# DefuseIt01.net
KiCad netlist of a schematic drawn in EAGLE
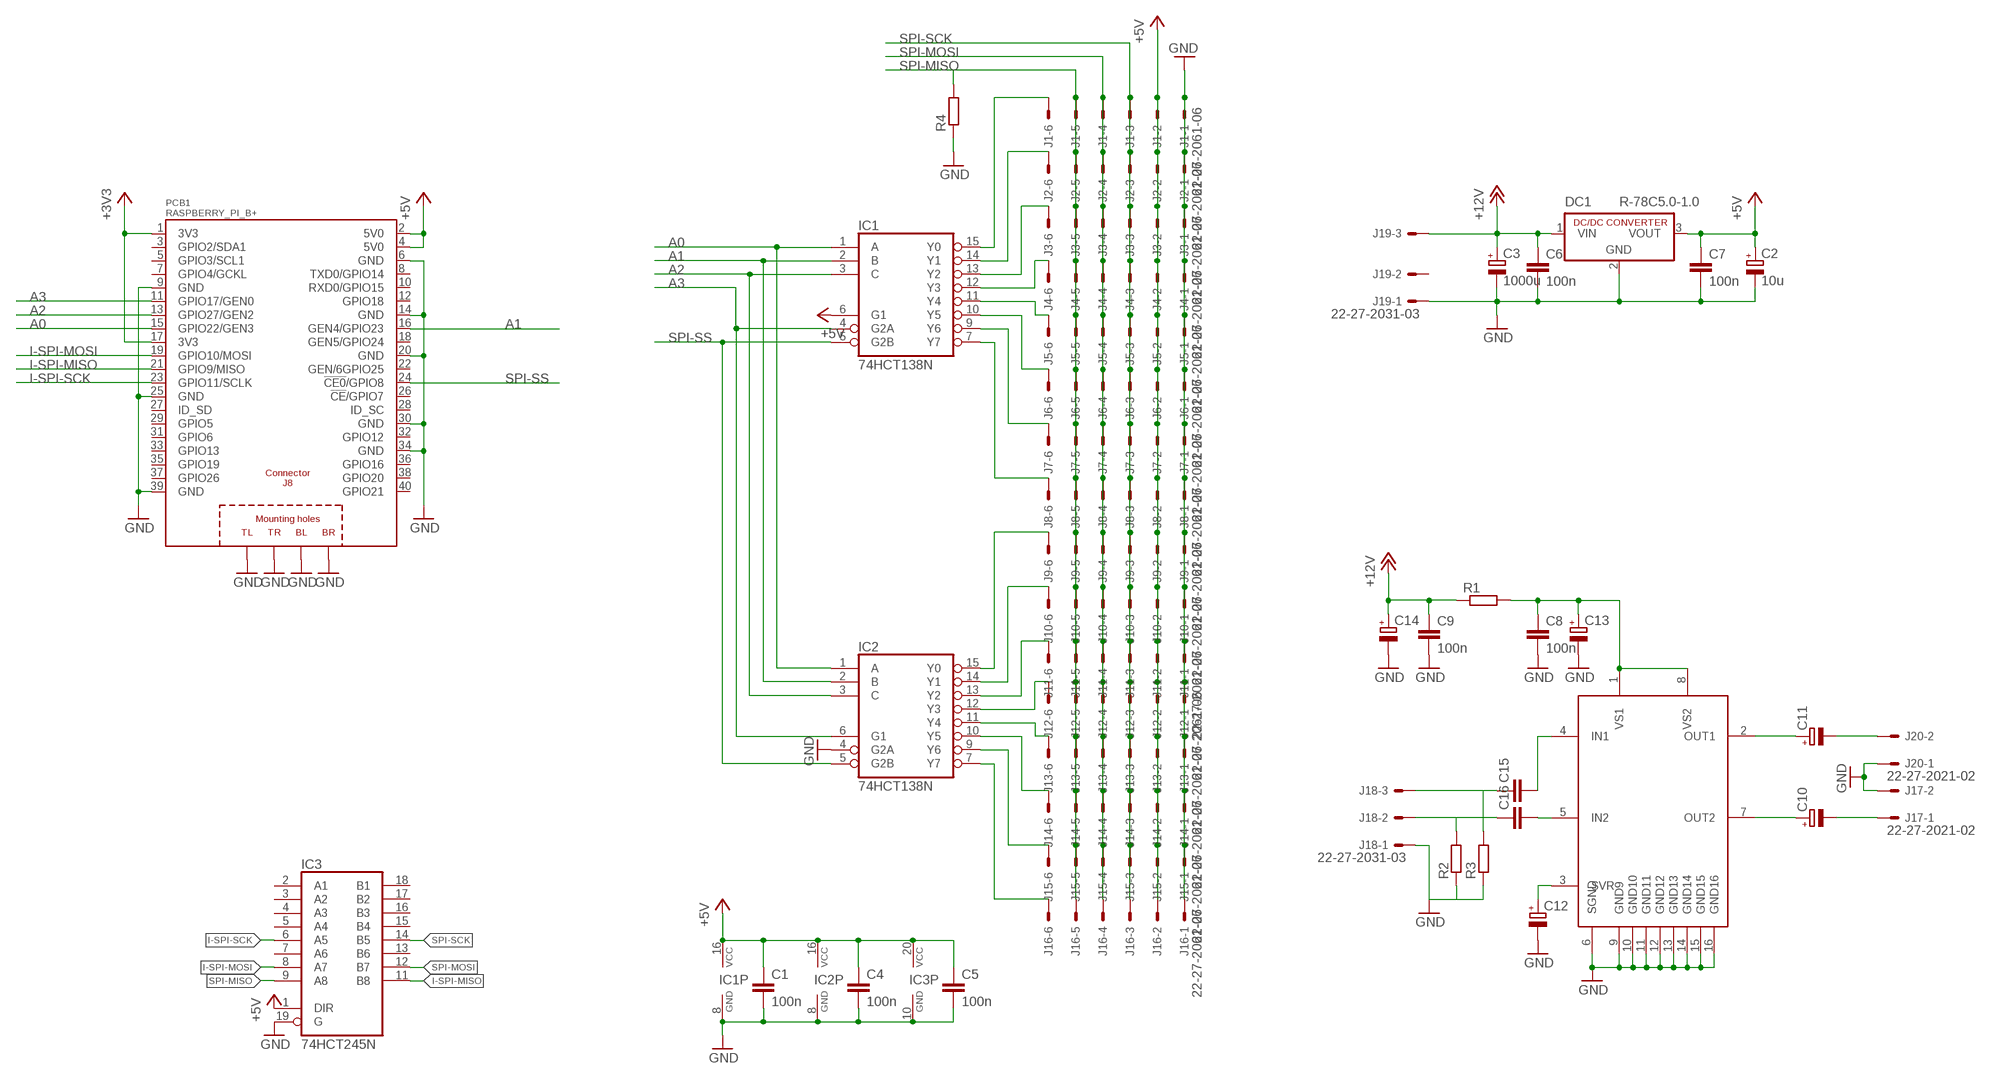
[diagram p0: schematic, sheet 1]

(export (version "E")
  (design (tool "Eeschema 10.0.6"))
  (components
    (comp (ref "C1")
      (value "100n")
      (footprint "eagle-import:C025-025X050")
      (libsource (lib "eagle-import") (part "C-EU025-025X050"))
    )
    (comp (ref "C2")
      (value "10u")
      (footprint "eagle-import:E3,5-8")
      (libsource (lib "eagle-import") (part "CPOL-EUE3.5-8"))
    )
    (comp (ref "C3")
      (value "1000u")
      (footprint "eagle-import:E7,5-16")
      (libsource (lib "eagle-import") (part "CPOL-EUE7.5-16"))
    )
    (comp (ref "C4")
      (value "100n")
      (footprint "eagle-import:C025-025X050")
      (libsource (lib "eagle-import") (part "C-EU025-025X050"))
    )
    (comp (ref "C5")
      (value "100n")
      (footprint "eagle-import:C025-025X050")
      (libsource (lib "eagle-import") (part "C-EU025-025X050"))
    )
    (comp (ref "C6")
      (value "100n")
      (footprint "eagle-import:C025-025X050")
      (libsource (lib "eagle-import") (part "C-EU025-025X050"))
    )
    (comp (ref "C7")
      (value "100n")
      (footprint "eagle-import:C025-025X050")
      (libsource (lib "eagle-import") (part "C-EU025-025X050"))
    )
    (comp (ref "C8")
      (value "100n")
      (footprint "eagle-import:C025-025X050")
      (libsource (lib "eagle-import") (part "C-EU025-025X050"))
    )
    (comp (ref "C9")
      (value "100n")
      (footprint "eagle-import:C025-025X050")
      (libsource (lib "eagle-import") (part "C-EU025-025X050"))
    )
    (comp (ref "C10")
      (value "CPOL-EUE3.5-8")
      (footprint "eagle-import:E3,5-8")
      (libsource (lib "eagle-import") (part "CPOL-EUE3.5-8"))
    )
    (comp (ref "C11")
      (value "CPOL-EUE3.5-8")
      (footprint "eagle-import:E3,5-8")
      (libsource (lib "eagle-import") (part "CPOL-EUE3.5-8"))
    )
    (comp (ref "C12")
      (value "CPOL-EUE2.5-5")
      (footprint "eagle-import:E2,5-5")
      (libsource (lib "eagle-import") (part "CPOL-EUE2.5-5"))
    )
    (comp (ref "C13")
      (value "CPOL-EUE2.5-5")
      (footprint "eagle-import:E2,5-5")
      (libsource (lib "eagle-import") (part "CPOL-EUE2.5-5"))
    )
    (comp (ref "C14")
      (value "CPOL-EUE2.5-5")
      (footprint "eagle-import:E2,5-5")
      (libsource (lib "eagle-import") (part "CPOL-EUE2.5-5"))
    )
    (comp (ref "C15")
      (value "C-EU050-030X075")
      (footprint "eagle-import:C050-030X075")
      (libsource (lib "eagle-import") (part "C-EU050-030X075"))
    )
    (comp (ref "C16")
      (value "C-EU050-030X075")
      (footprint "eagle-import:C050-030X075")
      (libsource (lib "eagle-import") (part "C-EU050-030X075"))
    )
    (comp (ref "DC1")
      (value "R-78C5.0-1.0")
      (footprint "eagle-import:SIP3")
      (libsource (lib "eagle-import") (part "R-78C-1.05.0"))
    )
    (comp (ref "IC1")
      (value "74HCT138N")
      (footprint "eagle-import:DIL16")
      (libsource (lib "eagle-import") (part "74138NHCT"))
    )
    (comp (ref "IC2")
      (value "74HCT138N")
      (footprint "eagle-import:DIL16")
      (libsource (lib "eagle-import") (part "74138NHCT"))
    )
    (comp (ref "IC3")
      (value "74HCT245N")
      (footprint "eagle-import:DIL20")
      (libsource (lib "eagle-import") (part "74245NHCT"))
    )
    (comp (ref "J1")
      (value "22-27-2061-06")
      (footprint "eagle-import:6410-06")
      (libsource (lib "eagle-import") (part "22-?-0627-2061"))
    )
    (comp (ref "J2")
      (value "22-27-2061-06")
      (footprint "eagle-import:6410-06")
      (libsource (lib "eagle-import") (part "22-?-0627-2061"))
    )
    (comp (ref "J3")
      (value "22-27-2061-06")
      (footprint "eagle-import:6410-06")
      (libsource (lib "eagle-import") (part "22-?-0627-2061"))
    )
    (comp (ref "J4")
      (value "22-27-2061-06")
      (footprint "eagle-import:6410-06")
      (libsource (lib "eagle-import") (part "22-?-0627-2061"))
    )
    (comp (ref "J5")
      (value "22-27-2061-06")
      (footprint "eagle-import:6410-06")
      (libsource (lib "eagle-import") (part "22-?-0627-2061"))
    )
    (comp (ref "J6")
      (value "22-27-2061-06")
      (footprint "eagle-import:6410-06")
      (libsource (lib "eagle-import") (part "22-?-0627-2061"))
    )
    (comp (ref "J7")
      (value "22-27-2061-06")
      (footprint "eagle-import:6410-06")
      (libsource (lib "eagle-import") (part "22-?-0627-2061"))
    )
    (comp (ref "J8")
      (value "22-27-2061-06")
      (footprint "eagle-import:6410-06")
      (libsource (lib "eagle-import") (part "22-?-0627-2061"))
    )
    (comp (ref "J9")
      (value "22-27-2061-06")
      (footprint "eagle-import:6410-06")
      (libsource (lib "eagle-import") (part "22-?-0627-2061"))
    )
    (comp (ref "J10")
      (value "22-27-2061-06")
      (footprint "eagle-import:6410-06")
      (libsource (lib "eagle-import") (part "22-?-0627-2061"))
    )
    (comp (ref "J11")
      (value "22-27-2061-06")
      (footprint "eagle-import:6410-06")
      (libsource (lib "eagle-import") (part "22-?-0627-2061"))
    )
    (comp (ref "J12")
      (value "22-27-2061-06")
      (footprint "eagle-import:6410-06")
      (libsource (lib "eagle-import") (part "22-?-0627-2061"))
    )
    (comp (ref "J13")
      (value "22-27-2061-06")
      (footprint "eagle-import:6410-06")
      (libsource (lib "eagle-import") (part "22-?-0627-2061"))
    )
    (comp (ref "J14")
      (value "22-27-2061-06")
      (footprint "eagle-import:6410-06")
      (libsource (lib "eagle-import") (part "22-?-0627-2061"))
    )
    (comp (ref "J15")
      (value "22-27-2061-06")
      (footprint "eagle-import:6410-06")
      (libsource (lib "eagle-import") (part "22-?-0627-2061"))
    )
    (comp (ref "J16")
      (value "22-27-2061-06")
      (footprint "eagle-import:6410-06")
      (libsource (lib "eagle-import") (part "22-?-0627-2061"))
    )
    (comp (ref "J17")
      (value "22-27-2021-02")
      (footprint "eagle-import:6410-02")
      (libsource (lib "eagle-import") (part "22-?-0227-2021"))
    )
    (comp (ref "J18")
      (value "22-27-2031-03")
      (footprint "eagle-import:6410-03")
      (libsource (lib "eagle-import") (part "22-?-0327-2031"))
    )
    (comp (ref "J19")
      (value "22-27-2031-03")
      (footprint "eagle-import:6410-03")
      (libsource (lib "eagle-import") (part "22-?-0327-2031"))
    )
    (comp (ref "J20")
      (value "22-27-2021-02")
      (footprint "eagle-import:6410-02")
      (libsource (lib "eagle-import") (part "22-?-0227-2021"))
    )
    (comp (ref "PCB1")
      (value "RASPBERRY_PI_B+")
      (footprint "eagle-import:RASPBERRY_PI_B+")
      (libsource (lib "eagle-import") (part "RASPBERRY_PI_B+"))
    )
    (comp (ref "R1")
      (value "R-EU_0207/10")
      (footprint "eagle-import:0207_10")
      (libsource (lib "eagle-import") (part "R-EU_0207/10"))
    )
    (comp (ref "R2")
      (value "R-EU_0207/10")
      (footprint "eagle-import:0207_10")
      (libsource (lib "eagle-import") (part "R-EU_0207/10"))
    )
    (comp (ref "R3")
      (value "R-EU_0207/10")
      (footprint "eagle-import:0207_10")
      (libsource (lib "eagle-import") (part "R-EU_0207/10"))
    )
    (comp (ref "R4")
      (value "R-EU_0207/10")
      (footprint "eagle-import:0207_10")
      (libsource (lib "eagle-import") (part "R-EU_0207/10"))
    )
    (comp (ref "U$1")
      (value "TDA7268")
      (footprint "eagle-import:DIL16")
      (libsource (lib "eagle-import") (part "TDA7268"))
    )
  )
  (nets
    (net (code "1") (name "+3V3") (class "Default")
      (node (ref "PCB1") (pin "1") (pinfunction "3V3_1") (pintype "power_in"))
      (node (ref "PCB1") (pin "17") (pinfunction "3V3_17") (pintype "power_in"))
    )
    (net (code "2") (name "+5V") (class "Default")
      (node (ref "C1") (pin "1") (pinfunction "1_1") (pintype "passive"))
      (node (ref "C2") (pin "+") (pinfunction "+_+") (pintype "passive"))
      (node (ref "C4") (pin "1") (pinfunction "1_1") (pintype "passive"))
      (node (ref "C5") (pin "1") (pinfunction "1_1") (pintype "passive"))
      (node (ref "C7") (pin "1") (pinfunction "1_1") (pintype "passive"))
      (node (ref "DC1") (pin "3") (pinfunction "VOUT_3") (pintype "passive"))
      (node (ref "IC1") (pin "16") (pinfunction "VCC_16") (pintype "power_in"))
      (node (ref "IC1") (pin "6") (pinfunction "G1_6") (pintype "input"))
      (node (ref "IC2") (pin "16") (pinfunction "VCC_16") (pintype "power_in"))
      (node (ref "IC3") (pin "1") (pinfunction "DIR_1") (pintype "input"))
      (node (ref "IC3") (pin "20") (pinfunction "VCC_20") (pintype "power_in"))
      (node (ref "J1") (pin "2") (pinfunction "S_2") (pintype "passive"))
      (node (ref "J10") (pin "2") (pinfunction "S_2") (pintype "passive"))
      (node (ref "J11") (pin "2") (pinfunction "S_2") (pintype "passive"))
      (node (ref "J12") (pin "2") (pinfunction "S_2") (pintype "passive"))
      (node (ref "J13") (pin "2") (pinfunction "S_2") (pintype "passive"))
      (node (ref "J14") (pin "2") (pinfunction "S_2") (pintype "passive"))
      (node (ref "J15") (pin "2") (pinfunction "S_2") (pintype "passive"))
      (node (ref "J16") (pin "2") (pinfunction "S_2") (pintype "passive"))
      (node (ref "J2") (pin "2") (pinfunction "S_2") (pintype "passive"))
      (node (ref "J3") (pin "2") (pinfunction "S_2") (pintype "passive"))
      (node (ref "J4") (pin "2") (pinfunction "S_2") (pintype "passive"))
      (node (ref "J5") (pin "2") (pinfunction "S_2") (pintype "passive"))
      (node (ref "J6") (pin "2") (pinfunction "S_2") (pintype "passive"))
      (node (ref "J7") (pin "2") (pinfunction "S_2") (pintype "passive"))
      (node (ref "J8") (pin "2") (pinfunction "S_2") (pintype "passive"))
      (node (ref "J9") (pin "2") (pinfunction "S_2") (pintype "passive"))
      (node (ref "PCB1") (pin "2") (pinfunction "5V0_2") (pintype "power_in"))
      (node (ref "PCB1") (pin "4") (pinfunction "5V0_4") (pintype "power_in"))
    )
    (net (code "3") (name "+12V") (class "Default")
      (node (ref "C14") (pin "+") (pinfunction "+_+") (pintype "passive"))
      (node (ref "C3") (pin "+") (pinfunction "+_+") (pintype "passive"))
      (node (ref "C6") (pin "1") (pinfunction "1_1") (pintype "passive"))
      (node (ref "C9") (pin "1") (pinfunction "1_1") (pintype "passive"))
      (node (ref "DC1") (pin "1") (pinfunction "VIN_1") (pintype "passive"))
      (node (ref "J19") (pin "3") (pinfunction "S_3") (pintype "passive"))
      (node (ref "R1") (pin "1") (pinfunction "1_1") (pintype "passive"))
    )
    (net (code "4") (name "/A0") (class "Default")
      (node (ref "IC1") (pin "1") (pinfunction "A_1") (pintype "input"))
      (node (ref "IC2") (pin "1") (pinfunction "A_1") (pintype "input"))
      (node (ref "PCB1") (pin "15") (pinfunction "GPIO22/GEN3_15") (pintype "bidirectional"))
    )
    (net (code "5") (name "/A1") (class "Default")
      (node (ref "IC1") (pin "2") (pinfunction "B_2") (pintype "input"))
      (node (ref "IC2") (pin "2") (pinfunction "B_2") (pintype "input"))
      (node (ref "PCB1") (pin "16") (pinfunction "GEN4/GPIO23_16") (pintype "bidirectional"))
    )
    (net (code "6") (name "/A2") (class "Default")
      (node (ref "IC1") (pin "3") (pinfunction "C_3") (pintype "input"))
      (node (ref "IC2") (pin "3") (pinfunction "C_3") (pintype "input"))
      (node (ref "PCB1") (pin "13") (pinfunction "GPIO27/GEN2_13") (pintype "bidirectional"))
    )
    (net (code "7") (name "/A3") (class "Default")
      (node (ref "IC1") (pin "4") (pinfunction "G2A_4") (pintype "input"))
      (node (ref "IC2") (pin "6") (pinfunction "G1_6") (pintype "input"))
      (node (ref "PCB1") (pin "11") (pinfunction "GPIO17/GEN0_11") (pintype "bidirectional"))
    )
    (net (code "8") (name "/SPI-SS") (class "Default")
      (node (ref "IC1") (pin "5") (pinfunction "G2B_5") (pintype "input"))
      (node (ref "IC2") (pin "5") (pinfunction "G2B_5") (pintype "input"))
      (node (ref "PCB1") (pin "24") (pinfunction "~{CE0}/GPIO8_24") (pintype "bidirectional"))
    )
    (net (code "9") (name "GND") (class "Default")
      (node (ref "C1") (pin "2") (pinfunction "2_2") (pintype "passive"))
      (node (ref "C12") (pin "-") (pinfunction "-_-") (pintype "passive"))
      (node (ref "C13") (pin "-") (pinfunction "-_-") (pintype "passive"))
      (node (ref "C14") (pin "-") (pinfunction "-_-") (pintype "passive"))
      (node (ref "C2") (pin "-") (pinfunction "-_-") (pintype "passive"))
      (node (ref "C3") (pin "-") (pinfunction "-_-") (pintype "passive"))
      (node (ref "C4") (pin "2") (pinfunction "2_2") (pintype "passive"))
      (node (ref "C5") (pin "2") (pinfunction "2_2") (pintype "passive"))
      (node (ref "C6") (pin "2") (pinfunction "2_2") (pintype "passive"))
      (node (ref "C7") (pin "2") (pinfunction "2_2") (pintype "passive"))
      (node (ref "C8") (pin "2") (pinfunction "2_2") (pintype "passive"))
      (node (ref "C9") (pin "2") (pinfunction "2_2") (pintype "passive"))
      (node (ref "DC1") (pin "2") (pinfunction "GND_2") (pintype "passive"))
      (node (ref "IC1") (pin "8") (pinfunction "GND_8") (pintype "power_in"))
      (node (ref "IC2") (pin "4") (pinfunction "G2A_4") (pintype "input"))
      (node (ref "IC2") (pin "8") (pinfunction "GND_8") (pintype "power_in"))
      (node (ref "IC3") (pin "10") (pinfunction "GND_10") (pintype "power_in"))
      (node (ref "IC3") (pin "19") (pinfunction "G_19") (pintype "input"))
      (node (ref "J1") (pin "1") (pinfunction "S_1") (pintype "passive"))
      (node (ref "J10") (pin "1") (pinfunction "S_1") (pintype "passive"))
      (node (ref "J11") (pin "1") (pinfunction "S_1") (pintype "passive"))
      (node (ref "J12") (pin "1") (pinfunction "S_1") (pintype "passive"))
      (node (ref "J13") (pin "1") (pinfunction "S_1") (pintype "passive"))
      (node (ref "J14") (pin "1") (pinfunction "S_1") (pintype "passive"))
      (node (ref "J15") (pin "1") (pinfunction "S_1") (pintype "passive"))
      (node (ref "J16") (pin "1") (pinfunction "S_1") (pintype "passive"))
      (node (ref "J17") (pin "2") (pinfunction "S_2") (pintype "passive"))
      (node (ref "J18") (pin "1") (pinfunction "S_1") (pintype "passive"))
      (node (ref "J19") (pin "1") (pinfunction "S_1") (pintype "passive"))
      (node (ref "J2") (pin "1") (pinfunction "S_1") (pintype "passive"))
      (node (ref "J20") (pin "1") (pinfunction "S_1") (pintype "passive"))
      (node (ref "J3") (pin "1") (pinfunction "S_1") (pintype "passive"))
      (node (ref "J4") (pin "1") (pinfunction "S_1") (pintype "passive"))
      (node (ref "J5") (pin "1") (pinfunction "S_1") (pintype "passive"))
      (node (ref "J6") (pin "1") (pinfunction "S_1") (pintype "passive"))
      (node (ref "J7") (pin "1") (pinfunction "S_1") (pintype "passive"))
      (node (ref "J8") (pin "1") (pinfunction "S_1") (pintype "passive"))
      (node (ref "J9") (pin "1") (pinfunction "S_1") (pintype "passive"))
      (node (ref "PCB1") (pin "14") (pinfunction "GND_14") (pintype "power_in"))
      (node (ref "PCB1") (pin "20") (pinfunction "GND_20") (pintype "power_in"))
      (node (ref "PCB1") (pin "25") (pinfunction "GND_25") (pintype "power_in"))
      (node (ref "PCB1") (pin "30") (pinfunction "GND_30") (pintype "power_in"))
      (node (ref "PCB1") (pin "34") (pinfunction "GND_34") (pintype "power_in"))
      (node (ref "PCB1") (pin "39") (pinfunction "GND_39") (pintype "power_in"))
      (node (ref "PCB1") (pin "6") (pinfunction "GND_6") (pintype "power_in"))
      (node (ref "PCB1") (pin "9") (pinfunction "GND_9") (pintype "power_in"))
      (node (ref "PCB1") (pin "PE_BL") (pinfunction "BL_PE_BL") (pintype "bidirectional"))
      (node (ref "PCB1") (pin "PE_BR") (pinfunction "BR_PE_BR") (pintype "bidirectional"))
      (node (ref "PCB1") (pin "PE_TL") (pinfunction "TL_PE_TL") (pintype "bidirectional"))
      (node (ref "PCB1") (pin "PE_TR") (pinfunction "TR_PE_TR") (pintype "bidirectional"))
      (node (ref "R2") (pin "1") (pinfunction "1_1") (pintype "passive"))
      (node (ref "R3") (pin "1") (pinfunction "1_1") (pintype "passive"))
      (node (ref "R4") (pin "1") (pinfunction "1_1") (pintype "passive"))
      (node (ref "U$1") (pin "10") (pinfunction "GND10_10") (pintype "bidirectional"))
      (node (ref "U$1") (pin "11") (pinfunction "GND11_11") (pintype "bidirectional"))
      (node (ref "U$1") (pin "12") (pinfunction "GND12_12") (pintype "bidirectional"))
      (node (ref "U$1") (pin "13") (pinfunction "GND13_13") (pintype "bidirectional"))
      (node (ref "U$1") (pin "14") (pinfunction "GND14_14") (pintype "bidirectional"))
      (node (ref "U$1") (pin "15") (pinfunction "GND15_15") (pintype "bidirectional"))
      (node (ref "U$1") (pin "16") (pinfunction "GND16_16") (pintype "bidirectional"))
      (node (ref "U$1") (pin "6") (pinfunction "SGND_6") (pintype "bidirectional"))
      (node (ref "U$1") (pin "9") (pinfunction "GND9_9") (pintype "bidirectional"))
    )
    (net (code "10") (name "I-SPI-MISO") (class "Default")
      (node (ref "IC3") (pin "11") (pinfunction "B8_11") (pintype "bidirectional"))
      (node (ref "PCB1") (pin "21") (pinfunction "GPIO9/MISO_21") (pintype "bidirectional"))
    )
    (net (code "11") (name "I-SPI-MOSI") (class "Default")
      (node (ref "IC3") (pin "8") (pinfunction "A7_8") (pintype "bidirectional"))
      (node (ref "PCB1") (pin "19") (pinfunction "GPIO10/MOSI_19") (pintype "bidirectional"))
    )
    (net (code "12") (name "I-SPI-SCK") (class "Default")
      (node (ref "IC3") (pin "6") (pinfunction "A5_6") (pintype "bidirectional"))
      (node (ref "PCB1") (pin "23") (pinfunction "GPIO11/SCLK_23") (pintype "bidirectional"))
    )
    (net (code "13") (name "Net-(IC1A-Y0)") (class "Default")
      (node (ref "IC1") (pin "15") (pinfunction "Y0_15") (pintype "output"))
      (node (ref "J1") (pin "6") (pinfunction "S_6") (pintype "passive"))
    )
    (net (code "14") (name "Net-(IC1A-Y1)") (class "Default")
      (node (ref "IC1") (pin "14") (pinfunction "Y1_14") (pintype "output"))
      (node (ref "J2") (pin "6") (pinfunction "S_6") (pintype "passive"))
    )
    (net (code "15") (name "Net-(IC1A-Y2)") (class "Default")
      (node (ref "IC1") (pin "13") (pinfunction "Y2_13") (pintype "output"))
      (node (ref "J3") (pin "6") (pinfunction "S_6") (pintype "passive"))
    )
    (net (code "16") (name "Net-(IC1A-Y3)") (class "Default")
      (node (ref "IC1") (pin "12") (pinfunction "Y3_12") (pintype "output"))
      (node (ref "J4") (pin "6") (pinfunction "S_6") (pintype "passive"))
    )
    (net (code "17") (name "Net-(IC1A-Y4)") (class "Default")
      (node (ref "IC1") (pin "11") (pinfunction "Y4_11") (pintype "output"))
      (node (ref "J5") (pin "6") (pinfunction "S_6") (pintype "passive"))
    )
    (net (code "18") (name "Net-(IC1A-Y5)") (class "Default")
      (node (ref "IC1") (pin "10") (pinfunction "Y5_10") (pintype "output"))
      (node (ref "J6") (pin "6") (pinfunction "S_6") (pintype "passive"))
    )
    (net (code "19") (name "Net-(IC1A-Y6)") (class "Default")
      (node (ref "IC1") (pin "9") (pinfunction "Y6_9") (pintype "output"))
      (node (ref "J7") (pin "6") (pinfunction "S_6") (pintype "passive"))
    )
    (net (code "20") (name "Net-(IC1A-Y7)") (class "Default")
      (node (ref "IC1") (pin "7") (pinfunction "Y7_7") (pintype "output"))
      (node (ref "J8") (pin "6") (pinfunction "S_6") (pintype "passive"))
    )
    (net (code "21") (name "Net-(IC2A-Y0)") (class "Default")
      (node (ref "IC2") (pin "15") (pinfunction "Y0_15") (pintype "output"))
      (node (ref "J9") (pin "6") (pinfunction "S_6") (pintype "passive"))
    )
    (net (code "22") (name "Net-(IC2A-Y1)") (class "Default")
      (node (ref "IC2") (pin "14") (pinfunction "Y1_14") (pintype "output"))
      (node (ref "J10") (pin "6") (pinfunction "S_6") (pintype "passive"))
    )
    (net (code "23") (name "Net-(IC2A-Y2)") (class "Default")
      (node (ref "IC2") (pin "13") (pinfunction "Y2_13") (pintype "output"))
      (node (ref "J11") (pin "6") (pinfunction "S_6") (pintype "passive"))
    )
    (net (code "24") (name "Net-(IC2A-Y3)") (class "Default")
      (node (ref "IC2") (pin "12") (pinfunction "Y3_12") (pintype "output"))
      (node (ref "J12") (pin "6") (pinfunction "S_6") (pintype "passive"))
    )
    (net (code "25") (name "Net-(IC2A-Y4)") (class "Default")
      (node (ref "IC2") (pin "11") (pinfunction "Y4_11") (pintype "output"))
      (node (ref "J13") (pin "6") (pinfunction "S_6") (pintype "passive"))
    )
    (net (code "26") (name "Net-(IC2A-Y5)") (class "Default")
      (node (ref "IC2") (pin "10") (pinfunction "Y5_10") (pintype "output"))
      (node (ref "J14") (pin "6") (pinfunction "S_6") (pintype "passive"))
    )
    (net (code "27") (name "Net-(IC2A-Y6)") (class "Default")
      (node (ref "IC2") (pin "9") (pinfunction "Y6_9") (pintype "output"))
      (node (ref "J15") (pin "6") (pinfunction "S_6") (pintype "passive"))
    )
    (net (code "28") (name "Net-(IC2A-Y7)") (class "Default")
      (node (ref "IC2") (pin "7") (pinfunction "Y7_7") (pintype "output"))
      (node (ref "J16") (pin "6") (pinfunction "S_6") (pintype "passive"))
    )
    (net (code "29") (name "Net-(J17A-S)") (class "Default")
      (node (ref "C10") (pin "-") (pinfunction "-_-") (pintype "passive"))
      (node (ref "J17") (pin "1") (pinfunction "S_1") (pintype "passive"))
    )
    (net (code "30") (name "Net-(J18B-S)") (class "Default")
      (node (ref "C16") (pin "1") (pinfunction "1_1") (pintype "passive"))
      (node (ref "J18") (pin "2") (pinfunction "S_2") (pintype "passive"))
      (node (ref "R2") (pin "2") (pinfunction "2_2") (pintype "passive"))
    )
    (net (code "31") (name "Net-(J18C-S)") (class "Default")
      (node (ref "C15") (pin "1") (pinfunction "1_1") (pintype "passive"))
      (node (ref "J18") (pin "3") (pinfunction "S_3") (pintype "passive"))
      (node (ref "R3") (pin "2") (pinfunction "2_2") (pintype "passive"))
    )
    (net (code "32") (name "Net-(J20B-S)") (class "Default")
      (node (ref "C11") (pin "-") (pinfunction "-_-") (pintype "passive"))
      (node (ref "J20") (pin "2") (pinfunction "S_2") (pintype "passive"))
    )
    (net (code "33") (name "Net-(U$1-IN1)") (class "Default")
      (node (ref "C15") (pin "2") (pinfunction "2_2") (pintype "passive"))
      (node (ref "U$1") (pin "4") (pinfunction "IN1_4") (pintype "bidirectional"))
    )
    (net (code "34") (name "Net-(U$1-IN2)") (class "Default")
      (node (ref "C16") (pin "2") (pinfunction "2_2") (pintype "passive"))
      (node (ref "U$1") (pin "5") (pinfunction "IN2_5") (pintype "bidirectional"))
    )
    (net (code "35") (name "Net-(U$1-OUT1)") (class "Default")
      (node (ref "C11") (pin "+") (pinfunction "+_+") (pintype "passive"))
      (node (ref "U$1") (pin "2") (pinfunction "OUT1_2") (pintype "bidirectional"))
    )
    (net (code "36") (name "Net-(U$1-OUT2)") (class "Default")
      (node (ref "C10") (pin "+") (pinfunction "+_+") (pintype "passive"))
      (node (ref "U$1") (pin "7") (pinfunction "OUT2_7") (pintype "bidirectional"))
    )
    (net (code "37") (name "Net-(U$1-SVR)") (class "Default")
      (node (ref "C12") (pin "+") (pinfunction "+_+") (pintype "passive"))
      (node (ref "U$1") (pin "3") (pinfunction "SVR_3") (pintype "bidirectional"))
    )
    (net (code "38") (name "Net-(U$1-VS1)") (class "Default")
      (node (ref "C13") (pin "+") (pinfunction "+_+") (pintype "passive"))
      (node (ref "C8") (pin "1") (pinfunction "1_1") (pintype "passive"))
      (node (ref "R1") (pin "2") (pinfunction "2_2") (pintype "passive"))
      (node (ref "U$1") (pin "1") (pinfunction "VS1_1") (pintype "bidirectional"))
      (node (ref "U$1") (pin "8") (pinfunction "VS2_8") (pintype "bidirectional"))
    )
    (net (code "39") (name "SPI-MISO") (class "Default")
      (node (ref "IC3") (pin "9") (pinfunction "A8_9") (pintype "bidirectional"))
      (node (ref "J1") (pin "5") (pinfunction "S_5") (pintype "passive"))
      (node (ref "J10") (pin "5") (pinfunction "S_5") (pintype "passive"))
      (node (ref "J11") (pin "5") (pinfunction "S_5") (pintype "passive"))
      (node (ref "J12") (pin "5") (pinfunction "S_5") (pintype "passive"))
      (node (ref "J13") (pin "5") (pinfunction "S_5") (pintype "passive"))
      (node (ref "J14") (pin "5") (pinfunction "S_5") (pintype "passive"))
      (node (ref "J15") (pin "5") (pinfunction "S_5") (pintype "passive"))
      (node (ref "J16") (pin "5") (pinfunction "S_5") (pintype "passive"))
      (node (ref "J2") (pin "5") (pinfunction "S_5") (pintype "passive"))
      (node (ref "J3") (pin "5") (pinfunction "S_5") (pintype "passive"))
      (node (ref "J4") (pin "5") (pinfunction "S_5") (pintype "passive"))
      (node (ref "J5") (pin "5") (pinfunction "S_5") (pintype "passive"))
      (node (ref "J6") (pin "5") (pinfunction "S_5") (pintype "passive"))
      (node (ref "J7") (pin "5") (pinfunction "S_5") (pintype "passive"))
      (node (ref "J8") (pin "5") (pinfunction "S_5") (pintype "passive"))
      (node (ref "J9") (pin "5") (pinfunction "S_5") (pintype "passive"))
      (node (ref "R4") (pin "2") (pinfunction "2_2") (pintype "passive"))
    )
    (net (code "40") (name "SPI-MOSI") (class "Default")
      (node (ref "IC3") (pin "12") (pinfunction "B7_12") (pintype "bidirectional"))
      (node (ref "J1") (pin "4") (pinfunction "S_4") (pintype "passive"))
      (node (ref "J10") (pin "4") (pinfunction "S_4") (pintype "passive"))
      (node (ref "J11") (pin "4") (pinfunction "S_4") (pintype "passive"))
      (node (ref "J12") (pin "4") (pinfunction "S_4") (pintype "passive"))
      (node (ref "J13") (pin "4") (pinfunction "S_4") (pintype "passive"))
      (node (ref "J14") (pin "4") (pinfunction "S_4") (pintype "passive"))
      (node (ref "J15") (pin "4") (pinfunction "S_4") (pintype "passive"))
      (node (ref "J16") (pin "4") (pinfunction "S_4") (pintype "passive"))
      (node (ref "J2") (pin "4") (pinfunction "S_4") (pintype "passive"))
      (node (ref "J3") (pin "4") (pinfunction "S_4") (pintype "passive"))
      (node (ref "J4") (pin "4") (pinfunction "S_4") (pintype "passive"))
      (node (ref "J5") (pin "4") (pinfunction "S_4") (pintype "passive"))
      (node (ref "J6") (pin "4") (pinfunction "S_4") (pintype "passive"))
      (node (ref "J7") (pin "4") (pinfunction "S_4") (pintype "passive"))
      (node (ref "J8") (pin "4") (pinfunction "S_4") (pintype "passive"))
      (node (ref "J9") (pin "4") (pinfunction "S_4") (pintype "passive"))
    )
    (net (code "41") (name "SPI-SCK") (class "Default")
      (node (ref "IC3") (pin "14") (pinfunction "B5_14") (pintype "bidirectional"))
      (node (ref "J1") (pin "3") (pinfunction "S_3") (pintype "passive"))
      (node (ref "J10") (pin "3") (pinfunction "S_3") (pintype "passive"))
      (node (ref "J11") (pin "3") (pinfunction "S_3") (pintype "passive"))
      (node (ref "J12") (pin "3") (pinfunction "S_3") (pintype "passive"))
      (node (ref "J13") (pin "3") (pinfunction "S_3") (pintype "passive"))
      (node (ref "J14") (pin "3") (pinfunction "S_3") (pintype "passive"))
      (node (ref "J15") (pin "3") (pinfunction "S_3") (pintype "passive"))
      (node (ref "J16") (pin "3") (pinfunction "S_3") (pintype "passive"))
      (node (ref "J2") (pin "3") (pinfunction "S_3") (pintype "passive"))
      (node (ref "J3") (pin "3") (pinfunction "S_3") (pintype "passive"))
      (node (ref "J4") (pin "3") (pinfunction "S_3") (pintype "passive"))
      (node (ref "J5") (pin "3") (pinfunction "S_3") (pintype "passive"))
      (node (ref "J6") (pin "3") (pinfunction "S_3") (pintype "passive"))
      (node (ref "J7") (pin "3") (pinfunction "S_3") (pintype "passive"))
      (node (ref "J8") (pin "3") (pinfunction "S_3") (pintype "passive"))
      (node (ref "J9") (pin "3") (pinfunction "S_3") (pintype "passive"))
    )
    (net (code "42") (name "unconnected-(IC3A-A1-Pad2)") (class "Default")
      (node (ref "IC3") (pin "2") (pinfunction "A1_2") (pintype "bidirectional"))
    )
    (net (code "43") (name "unconnected-(IC3A-A2-Pad3)") (class "Default")
      (node (ref "IC3") (pin "3") (pinfunction "A2_3") (pintype "bidirectional"))
    )
    (net (code "44") (name "unconnected-(IC3A-A3-Pad4)") (class "Default")
      (node (ref "IC3") (pin "4") (pinfunction "A3_4") (pintype "bidirectional"))
    )
    (net (code "45") (name "unconnected-(IC3A-A4-Pad5)") (class "Default")
      (node (ref "IC3") (pin "5") (pinfunction "A4_5") (pintype "bidirectional"))
    )
    (net (code "46") (name "unconnected-(IC3A-A6-Pad7)") (class "Default")
      (node (ref "IC3") (pin "7") (pinfunction "A6_7") (pintype "bidirectional"))
    )
    (net (code "47") (name "unconnected-(IC3A-B1-Pad18)") (class "Default")
      (node (ref "IC3") (pin "18") (pinfunction "B1_18") (pintype "bidirectional"))
    )
    (net (code "48") (name "unconnected-(IC3A-B2-Pad17)") (class "Default")
      (node (ref "IC3") (pin "17") (pinfunction "B2_17") (pintype "bidirectional"))
    )
    (net (code "49") (name "unconnected-(IC3A-B3-Pad16)") (class "Default")
      (node (ref "IC3") (pin "16") (pinfunction "B3_16") (pintype "bidirectional"))
    )
    (net (code "50") (name "unconnected-(IC3A-B4-Pad15)") (class "Default")
      (node (ref "IC3") (pin "15") (pinfunction "B4_15") (pintype "bidirectional"))
    )
    (net (code "51") (name "unconnected-(IC3A-B6-Pad13)") (class "Default")
      (node (ref "IC3") (pin "13") (pinfunction "B6_13") (pintype "bidirectional"))
    )
    (net (code "52") (name "unconnected-(J19B-S-Pad2)") (class "Default")
      (node (ref "J19") (pin "2") (pinfunction "S_2") (pintype "passive"))
    )
    (net (code "53") (name "unconnected-(PCB1-GEN5{slash}GPIO24-Pad18)") (class "Default")
      (node (ref "PCB1") (pin "18") (pinfunction "GEN5/GPIO24_18") (pintype "bidirectional"))
    )
    (net (code "54") (name "unconnected-(PCB1-GEN{slash}6GPIO25-Pad22)") (class "Default")
      (node (ref "PCB1") (pin "22") (pinfunction "GEN/6GPIO25_22") (pintype "bidirectional"))
    )
    (net (code "55") (name "unconnected-(PCB1-GPIO2{slash}SDA1-Pad3)") (class "Default")
      (node (ref "PCB1") (pin "3") (pinfunction "GPIO2/SDA1_3") (pintype "bidirectional"))
    )
    (net (code "56") (name "unconnected-(PCB1-GPIO3{slash}SCL1-Pad5)") (class "Default")
      (node (ref "PCB1") (pin "5") (pinfunction "GPIO3/SCL1_5") (pintype "bidirectional"))
    )
    (net (code "57") (name "unconnected-(PCB1-GPIO4{slash}GCKL-Pad7)") (class "Default")
      (node (ref "PCB1") (pin "7") (pinfunction "GPIO4/GCKL_7") (pintype "bidirectional"))
    )
    (net (code "58") (name "unconnected-(PCB1-GPIO5-Pad29)") (class "Default")
      (node (ref "PCB1") (pin "29") (pinfunction "GPIO5_29") (pintype "bidirectional"))
    )
    (net (code "59") (name "unconnected-(PCB1-GPIO6-Pad31)") (class "Default")
      (node (ref "PCB1") (pin "31") (pinfunction "GPIO6_31") (pintype "bidirectional"))
    )
    (net (code "60") (name "unconnected-(PCB1-GPIO12-Pad32)") (class "Default")
      (node (ref "PCB1") (pin "32") (pinfunction "GPIO12_32") (pintype "bidirectional"))
    )
    (net (code "61") (name "unconnected-(PCB1-GPIO13-Pad33)") (class "Default")
      (node (ref "PCB1") (pin "33") (pinfunction "GPIO13_33") (pintype "bidirectional"))
    )
    (net (code "62") (name "unconnected-(PCB1-GPIO16-Pad36)") (class "Default")
      (node (ref "PCB1") (pin "36") (pinfunction "GPIO16_36") (pintype "bidirectional"))
    )
    (net (code "63") (name "unconnected-(PCB1-GPIO18-Pad12)") (class "Default")
      (node (ref "PCB1") (pin "12") (pinfunction "GPIO18_12") (pintype "bidirectional"))
    )
    (net (code "64") (name "unconnected-(PCB1-GPIO19-Pad35)") (class "Default")
      (node (ref "PCB1") (pin "35") (pinfunction "GPIO19_35") (pintype "bidirectional"))
    )
    (net (code "65") (name "unconnected-(PCB1-GPIO20-Pad38)") (class "Default")
      (node (ref "PCB1") (pin "38") (pinfunction "GPIO20_38") (pintype "bidirectional"))
    )
    (net (code "66") (name "unconnected-(PCB1-GPIO21-Pad40)") (class "Default")
      (node (ref "PCB1") (pin "40") (pinfunction "GPIO21_40") (pintype "bidirectional"))
    )
    (net (code "67") (name "unconnected-(PCB1-GPIO26-Pad37)") (class "Default")
      (node (ref "PCB1") (pin "37") (pinfunction "GPIO26_37") (pintype "bidirectional"))
    )
    (net (code "68") (name "unconnected-(PCB1-ID_SC-Pad28)") (class "Default")
      (node (ref "PCB1") (pin "28") (pinfunction "ID_SC_28") (pintype "bidirectional"))
    )
    (net (code "69") (name "unconnected-(PCB1-ID_SD-Pad27)") (class "Default")
      (node (ref "PCB1") (pin "27") (pinfunction "ID_SD_27") (pintype "bidirectional"))
    )
    (net (code "70") (name "unconnected-(PCB1-RXD0{slash}GPIO15-Pad10)") (class "Default")
      (node (ref "PCB1") (pin "10") (pinfunction "RXD0/GPIO15_10") (pintype "bidirectional"))
    )
    (net (code "71") (name "unconnected-(PCB1-TXD0{slash}GPIO14-Pad8)") (class "Default")
      (node (ref "PCB1") (pin "8") (pinfunction "TXD0/GPIO14_8") (pintype "bidirectional"))
    )
    (net (code "72") (name "unconnected-(PCB1-~{CE}{slash}GPIO7-Pad26)") (class "Default")
      (node (ref "PCB1") (pin "26") (pinfunction "~{CE}/GPIO7_26") (pintype "bidirectional"))
    )
  )
)
